# Sheet4.net
KiCad netlist of a schematic drawn in Altium Designer
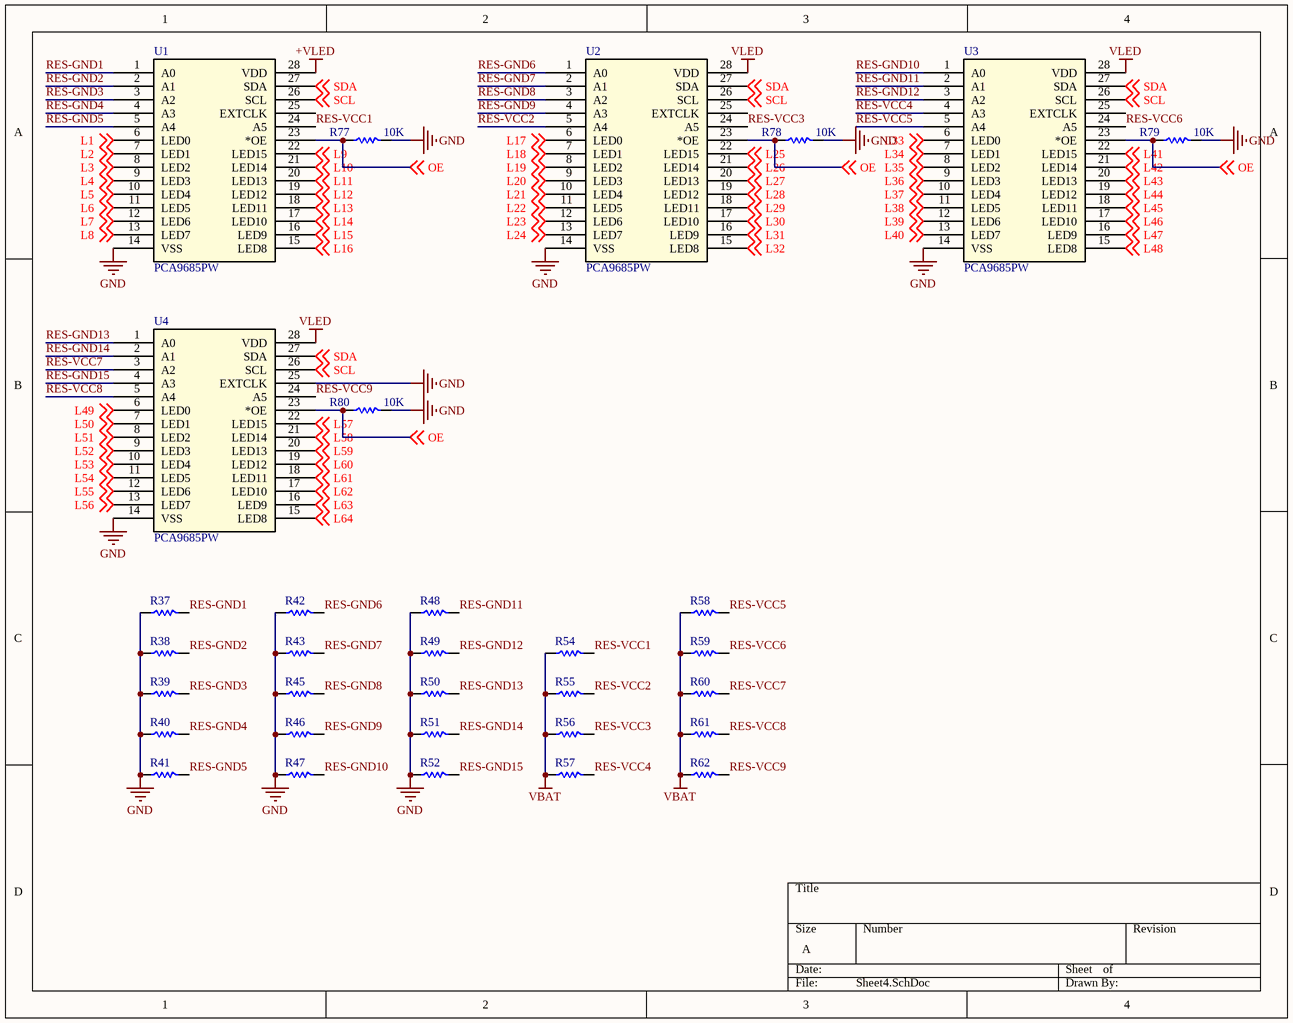
[diagram p0: Sheet4.SchDoc]

(export (version "E")
  (design (tool "Eeschema 10.0.6"))
  (components
    (comp (ref "R37")
      (value "10K")
      (footprint "R 0805")
      (description "Chip resistor")
      (fields (field (name "版权归属") "源创客"))
      (libsource (lib "Passive (Resistor-Capacitor-Inductor-Veristor-Ferrite)") (part "R"))
    )
    (comp (ref "R38")
      (value "10K")
      (footprint "R 0805")
      (description "Chip resistor")
      (fields (field (name "版权归属") "源创客"))
      (libsource (lib "Passive (Resistor-Capacitor-Inductor-Veristor-Ferrite)") (part "R"))
    )
    (comp (ref "R39")
      (value "10K")
      (footprint "R 0805")
      (description "Chip resistor")
      (fields (field (name "版权归属") "源创客"))
      (libsource (lib "Passive (Resistor-Capacitor-Inductor-Veristor-Ferrite)") (part "R"))
    )
    (comp (ref "R40")
      (value "10K")
      (footprint "R 0805")
      (description "Chip resistor")
      (fields (field (name "版权归属") "源创客"))
      (libsource (lib "Passive (Resistor-Capacitor-Inductor-Veristor-Ferrite)") (part "R"))
    )
    (comp (ref "R41")
      (value "10K")
      (footprint "R 0805")
      (description "Chip resistor")
      (fields (field (name "版权归属") "源创客"))
      (libsource (lib "Passive (Resistor-Capacitor-Inductor-Veristor-Ferrite)") (part "R"))
    )
    (comp (ref "R42")
      (value "10K")
      (footprint "R 0805")
      (description "Chip resistor")
      (fields (field (name "版权归属") "源创客"))
      (libsource (lib "Passive (Resistor-Capacitor-Inductor-Veristor-Ferrite)") (part "R"))
    )
    (comp (ref "R43")
      (value "10K")
      (footprint "R 0805")
      (description "Chip resistor")
      (fields (field (name "版权归属") "源创客"))
      (libsource (lib "Passive (Resistor-Capacitor-Inductor-Veristor-Ferrite)") (part "R"))
    )
    (comp (ref "R45")
      (value "10K")
      (footprint "R 0805")
      (description "Chip resistor")
      (fields (field (name "版权归属") "源创客"))
      (libsource (lib "Passive (Resistor-Capacitor-Inductor-Veristor-Ferrite)") (part "R"))
    )
    (comp (ref "R46")
      (value "10K")
      (footprint "R 0805")
      (description "Chip resistor")
      (fields (field (name "版权归属") "源创客"))
      (libsource (lib "Passive (Resistor-Capacitor-Inductor-Veristor-Ferrite)") (part "R"))
    )
    (comp (ref "R47")
      (value "10K")
      (footprint "R 0805")
      (description "Chip resistor")
      (fields (field (name "版权归属") "源创客"))
      (libsource (lib "Passive (Resistor-Capacitor-Inductor-Veristor-Ferrite)") (part "R"))
    )
    (comp (ref "R48")
      (value "10K")
      (footprint "R 0805")
      (description "Chip resistor")
      (fields (field (name "版权归属") "源创客"))
      (libsource (lib "Passive (Resistor-Capacitor-Inductor-Veristor-Ferrite)") (part "R"))
    )
    (comp (ref "R49")
      (value "10K")
      (footprint "R 0805")
      (description "Chip resistor")
      (fields (field (name "版权归属") "源创客"))
      (libsource (lib "Passive (Resistor-Capacitor-Inductor-Veristor-Ferrite)") (part "R"))
    )
    (comp (ref "R50")
      (value "10K")
      (footprint "R 0805")
      (description "Chip resistor")
      (fields (field (name "版权归属") "源创客"))
      (libsource (lib "Passive (Resistor-Capacitor-Inductor-Veristor-Ferrite)") (part "R"))
    )
    (comp (ref "R51")
      (value "10K")
      (footprint "R 0805")
      (description "Chip resistor")
      (fields (field (name "版权归属") "源创客"))
      (libsource (lib "Passive (Resistor-Capacitor-Inductor-Veristor-Ferrite)") (part "R"))
    )
    (comp (ref "R52")
      (value "10K")
      (footprint "R 0805")
      (description "Chip resistor")
      (fields (field (name "版权归属") "源创客"))
      (libsource (lib "Passive (Resistor-Capacitor-Inductor-Veristor-Ferrite)") (part "R"))
    )
    (comp (ref "R54")
      (value "10K")
      (footprint "R 0805")
      (description "Chip resistor")
      (fields (field (name "版权归属") "源创客"))
      (libsource (lib "Passive (Resistor-Capacitor-Inductor-Veristor-Ferrite)") (part "R"))
    )
    (comp (ref "R55")
      (value "10K")
      (footprint "R 0805")
      (description "Chip resistor")
      (fields (field (name "版权归属") "源创客"))
      (libsource (lib "Passive (Resistor-Capacitor-Inductor-Veristor-Ferrite)") (part "R"))
    )
    (comp (ref "R56")
      (value "10K")
      (footprint "R 0805")
      (description "Chip resistor")
      (fields (field (name "版权归属") "源创客"))
      (libsource (lib "Passive (Resistor-Capacitor-Inductor-Veristor-Ferrite)") (part "R"))
    )
    (comp (ref "R57")
      (value "10K")
      (footprint "R 0805")
      (description "Chip resistor")
      (fields (field (name "版权归属") "源创客"))
      (libsource (lib "Passive (Resistor-Capacitor-Inductor-Veristor-Ferrite)") (part "R"))
    )
    (comp (ref "R58")
      (value "10K")
      (footprint "R 0805")
      (description "Chip resistor")
      (fields (field (name "版权归属") "源创客"))
      (libsource (lib "Passive (Resistor-Capacitor-Inductor-Veristor-Ferrite)") (part "R"))
    )
    (comp (ref "R59")
      (value "10K")
      (footprint "R 0805")
      (description "Chip resistor")
      (fields (field (name "版权归属") "源创客"))
      (libsource (lib "Passive (Resistor-Capacitor-Inductor-Veristor-Ferrite)") (part "R"))
    )
    (comp (ref "R60")
      (value "10K")
      (footprint "R 0805")
      (description "Chip resistor")
      (fields (field (name "版权归属") "源创客"))
      (libsource (lib "Passive (Resistor-Capacitor-Inductor-Veristor-Ferrite)") (part "R"))
    )
    (comp (ref "R61")
      (value "10K")
      (footprint "R 0805")
      (description "Chip resistor")
      (fields (field (name "版权归属") "源创客"))
      (libsource (lib "Passive (Resistor-Capacitor-Inductor-Veristor-Ferrite)") (part "R"))
    )
    (comp (ref "R62")
      (value "10K")
      (footprint "R 0805")
      (description "Chip resistor")
      (fields (field (name "版权归属") "源创客"))
      (libsource (lib "Passive (Resistor-Capacitor-Inductor-Veristor-Ferrite)") (part "R"))
    )
    (comp (ref "R77")
      (value "10K")
      (footprint "R 0805")
      (description "Chip resistor")
      (fields (field (name "版权归属") "源创客"))
      (libsource (lib "Passive (Resistor-Capacitor-Inductor-Veristor-Ferrite)") (part "R"))
    )
    (comp (ref "R78")
      (value "10K")
      (footprint "R 0805")
      (description "Chip resistor")
      (fields (field (name "版权归属") "源创客"))
      (libsource (lib "Passive (Resistor-Capacitor-Inductor-Veristor-Ferrite)") (part "R"))
    )
    (comp (ref "R79")
      (value "10K")
      (footprint "R 0805")
      (description "Chip resistor")
      (fields (field (name "版权归属") "源创客"))
      (libsource (lib "Passive (Resistor-Capacitor-Inductor-Veristor-Ferrite)") (part "R"))
    )
    (comp (ref "R80")
      (value "10K")
      (footprint "R 0805")
      (description "Chip resistor")
      (fields (field (name "版权归属") "源创客"))
      (libsource (lib "Passive (Resistor-Capacitor-Inductor-Veristor-Ferrite)") (part "R"))
    )
    (comp (ref "U1")
      (value "PCA9685PW")
      (footprint "SOT361-1_NXP")
      (description "No Description Available")
      (fields (field (name "COPYRIGHT") "Copyright (C) 2018 Accelerated Designs. All rights reserved"))
      (libsource (lib "PCA9685") (part "PCA9685PW"))
    )
    (comp (ref "U2")
      (value "PCA9685PW")
      (footprint "SOT361-1_NXP")
      (description "No Description Available")
      (fields (field (name "COPYRIGHT") "Copyright (C) 2018 Accelerated Designs. All rights reserved"))
      (libsource (lib "PCA9685") (part "PCA9685PW"))
    )
    (comp (ref "U3")
      (value "PCA9685PW")
      (footprint "SOT361-1_NXP")
      (description "No Description Available")
      (fields (field (name "COPYRIGHT") "Copyright (C) 2018 Accelerated Designs. All rights reserved"))
      (libsource (lib "PCA9685") (part "PCA9685PW"))
    )
    (comp (ref "U4")
      (value "PCA9685PW")
      (footprint "SOT361-1_NXP")
      (description "No Description Available")
      (fields (field (name "COPYRIGHT") "Copyright (C) 2018 Accelerated Designs. All rights reserved"))
      (libsource (lib "PCA9685") (part "PCA9685PW"))
    )
  )
  (nets
    (net (code "1") (name "+VLED") (class "Default")
      (node (ref "U1") (pin "28") (pinfunction "VDD_28") (pintype "passive"))
    )
    (net (code "2") (name "/RES-GND1") (class "Default")
      (node (ref "R37") (pin "2") (pinfunction "2_2") (pintype "passive"))
      (node (ref "U1") (pin "1") (pinfunction "A0_1") (pintype "passive"))
    )
    (net (code "3") (name "/RES-GND2") (class "Default")
      (node (ref "R38") (pin "2") (pinfunction "2_2") (pintype "passive"))
      (node (ref "U1") (pin "2") (pinfunction "A1_2") (pintype "passive"))
    )
    (net (code "4") (name "/RES-GND3") (class "Default")
      (node (ref "R39") (pin "2") (pinfunction "2_2") (pintype "passive"))
      (node (ref "U1") (pin "3") (pinfunction "A2_3") (pintype "passive"))
    )
    (net (code "5") (name "/RES-GND4") (class "Default")
      (node (ref "R40") (pin "2") (pinfunction "2_2") (pintype "passive"))
      (node (ref "U1") (pin "4") (pinfunction "A3_4") (pintype "passive"))
    )
    (net (code "6") (name "/RES-GND5") (class "Default")
      (node (ref "R41") (pin "2") (pinfunction "2_2") (pintype "passive"))
      (node (ref "U1") (pin "5") (pinfunction "A4_5") (pintype "passive"))
    )
    (net (code "7") (name "/RES-GND6") (class "Default")
      (node (ref "R42") (pin "2") (pinfunction "2_2") (pintype "passive"))
      (node (ref "U2") (pin "1") (pinfunction "A0_1") (pintype "passive"))
    )
    (net (code "8") (name "/RES-GND7") (class "Default")
      (node (ref "R43") (pin "2") (pinfunction "2_2") (pintype "passive"))
      (node (ref "U2") (pin "2") (pinfunction "A1_2") (pintype "passive"))
    )
    (net (code "9") (name "/RES-GND8") (class "Default")
      (node (ref "R45") (pin "2") (pinfunction "2_2") (pintype "passive"))
      (node (ref "U2") (pin "3") (pinfunction "A2_3") (pintype "passive"))
    )
    (net (code "10") (name "/RES-GND9") (class "Default")
      (node (ref "R46") (pin "2") (pinfunction "2_2") (pintype "passive"))
      (node (ref "U2") (pin "4") (pinfunction "A3_4") (pintype "passive"))
    )
    (net (code "11") (name "/RES-GND10") (class "Default")
      (node (ref "R47") (pin "2") (pinfunction "2_2") (pintype "passive"))
      (node (ref "U3") (pin "1") (pinfunction "A0_1") (pintype "passive"))
    )
    (net (code "12") (name "/RES-GND11") (class "Default")
      (node (ref "R48") (pin "2") (pinfunction "2_2") (pintype "passive"))
      (node (ref "U3") (pin "2") (pinfunction "A1_2") (pintype "passive"))
    )
    (net (code "13") (name "/RES-GND12") (class "Default")
      (node (ref "R49") (pin "2") (pinfunction "2_2") (pintype "passive"))
      (node (ref "U3") (pin "3") (pinfunction "A2_3") (pintype "passive"))
    )
    (net (code "14") (name "/RES-GND13") (class "Default")
      (node (ref "R50") (pin "2") (pinfunction "2_2") (pintype "passive"))
      (node (ref "U4") (pin "1") (pinfunction "A0_1") (pintype "passive"))
    )
    (net (code "15") (name "/RES-GND14") (class "Default")
      (node (ref "R51") (pin "2") (pinfunction "2_2") (pintype "passive"))
      (node (ref "U4") (pin "2") (pinfunction "A1_2") (pintype "passive"))
    )
    (net (code "16") (name "/RES-GND15") (class "Default")
      (node (ref "R52") (pin "2") (pinfunction "2_2") (pintype "passive"))
      (node (ref "U4") (pin "4") (pinfunction "A3_4") (pintype "passive"))
    )
    (net (code "17") (name "/RES-VCC1") (class "Default")
      (node (ref "R54") (pin "2") (pinfunction "2_2") (pintype "passive"))
      (node (ref "U1") (pin "24") (pinfunction "A5_24") (pintype "passive"))
    )
    (net (code "18") (name "/RES-VCC2") (class "Default")
      (node (ref "R55") (pin "2") (pinfunction "2_2") (pintype "passive"))
      (node (ref "U2") (pin "5") (pinfunction "A4_5") (pintype "passive"))
    )
    (net (code "19") (name "/RES-VCC3") (class "Default")
      (node (ref "R56") (pin "2") (pinfunction "2_2") (pintype "passive"))
      (node (ref "U2") (pin "24") (pinfunction "A5_24") (pintype "passive"))
    )
    (net (code "20") (name "/RES-VCC4") (class "Default")
      (node (ref "R57") (pin "2") (pinfunction "2_2") (pintype "passive"))
      (node (ref "U3") (pin "4") (pinfunction "A3_4") (pintype "passive"))
    )
    (net (code "21") (name "/RES-VCC5") (class "Default")
      (node (ref "R58") (pin "2") (pinfunction "2_2") (pintype "passive"))
      (node (ref "U3") (pin "5") (pinfunction "A4_5") (pintype "passive"))
    )
    (net (code "22") (name "/RES-VCC6") (class "Default")
      (node (ref "R59") (pin "2") (pinfunction "2_2") (pintype "passive"))
      (node (ref "U3") (pin "24") (pinfunction "A5_24") (pintype "passive"))
    )
    (net (code "23") (name "/RES-VCC7") (class "Default")
      (node (ref "R60") (pin "2") (pinfunction "2_2") (pintype "passive"))
      (node (ref "U4") (pin "3") (pinfunction "A2_3") (pintype "passive"))
    )
    (net (code "24") (name "/RES-VCC8") (class "Default")
      (node (ref "R61") (pin "2") (pinfunction "2_2") (pintype "passive"))
      (node (ref "U4") (pin "5") (pinfunction "A4_5") (pintype "passive"))
    )
    (net (code "25") (name "/RES-VCC9") (class "Default")
      (node (ref "R62") (pin "2") (pinfunction "2_2") (pintype "passive"))
      (node (ref "U4") (pin "24") (pinfunction "A5_24") (pintype "passive"))
    )
    (net (code "26") (name "GND") (class "Default")
      (node (ref "R37") (pin "1") (pinfunction "1_1") (pintype "passive"))
      (node (ref "R38") (pin "1") (pinfunction "1_1") (pintype "passive"))
      (node (ref "R39") (pin "1") (pinfunction "1_1") (pintype "passive"))
      (node (ref "R40") (pin "1") (pinfunction "1_1") (pintype "passive"))
      (node (ref "R41") (pin "1") (pinfunction "1_1") (pintype "passive"))
      (node (ref "R42") (pin "1") (pinfunction "1_1") (pintype "passive"))
      (node (ref "R43") (pin "1") (pinfunction "1_1") (pintype "passive"))
      (node (ref "R45") (pin "1") (pinfunction "1_1") (pintype "passive"))
      (node (ref "R46") (pin "1") (pinfunction "1_1") (pintype "passive"))
      (node (ref "R47") (pin "1") (pinfunction "1_1") (pintype "passive"))
      (node (ref "R48") (pin "1") (pinfunction "1_1") (pintype "passive"))
      (node (ref "R49") (pin "1") (pinfunction "1_1") (pintype "passive"))
      (node (ref "R50") (pin "1") (pinfunction "1_1") (pintype "passive"))
      (node (ref "R51") (pin "1") (pinfunction "1_1") (pintype "passive"))
      (node (ref "R52") (pin "1") (pinfunction "1_1") (pintype "passive"))
      (node (ref "R77") (pin "2") (pinfunction "2_2") (pintype "passive"))
      (node (ref "R78") (pin "2") (pinfunction "2_2") (pintype "passive"))
      (node (ref "R79") (pin "2") (pinfunction "2_2") (pintype "passive"))
      (node (ref "R80") (pin "2") (pinfunction "2_2") (pintype "passive"))
      (node (ref "U1") (pin "14") (pinfunction "VSS_14") (pintype "passive"))
      (node (ref "U2") (pin "14") (pinfunction "VSS_14") (pintype "passive"))
      (node (ref "U3") (pin "14") (pinfunction "VSS_14") (pintype "passive"))
      (node (ref "U4") (pin "14") (pinfunction "VSS_14") (pintype "passive"))
      (node (ref "U4") (pin "25") (pinfunction "EXTCLK_25") (pintype "passive"))
    )
    (net (code "27") (name "L1") (class "Default")
      (node (ref "U1") (pin "6") (pinfunction "LED0_6") (pintype "passive"))
    )
    (net (code "28") (name "L2") (class "Default")
      (node (ref "U1") (pin "7") (pinfunction "LED1_7") (pintype "passive"))
    )
    (net (code "29") (name "L3") (class "Default")
      (node (ref "U1") (pin "8") (pinfunction "LED2_8") (pintype "passive"))
    )
    (net (code "30") (name "L4") (class "Default")
      (node (ref "U1") (pin "9") (pinfunction "LED3_9") (pintype "passive"))
    )
    (net (code "31") (name "L5") (class "Default")
      (node (ref "U1") (pin "10") (pinfunction "LED4_10") (pintype "passive"))
    )
    (net (code "32") (name "L6") (class "Default")
      (node (ref "U1") (pin "11") (pinfunction "LED5_11") (pintype "passive"))
    )
    (net (code "33") (name "L7") (class "Default")
      (node (ref "U1") (pin "12") (pinfunction "LED6_12") (pintype "passive"))
    )
    (net (code "34") (name "L8") (class "Default")
      (node (ref "U1") (pin "13") (pinfunction "LED7_13") (pintype "passive"))
    )
    (net (code "35") (name "L9") (class "Default")
      (node (ref "U1") (pin "22") (pinfunction "LED15_22") (pintype "passive"))
    )
    (net (code "36") (name "L10") (class "Default")
      (node (ref "U1") (pin "21") (pinfunction "LED14_21") (pintype "passive"))
    )
    (net (code "37") (name "L11") (class "Default")
      (node (ref "U1") (pin "20") (pinfunction "LED13_20") (pintype "passive"))
    )
    (net (code "38") (name "L12") (class "Default")
      (node (ref "U1") (pin "19") (pinfunction "LED12_19") (pintype "passive"))
    )
    (net (code "39") (name "L13") (class "Default")
      (node (ref "U1") (pin "18") (pinfunction "LED11_18") (pintype "passive"))
    )
    (net (code "40") (name "L14") (class "Default")
      (node (ref "U1") (pin "17") (pinfunction "LED10_17") (pintype "passive"))
    )
    (net (code "41") (name "L15") (class "Default")
      (node (ref "U1") (pin "16") (pinfunction "LED9_16") (pintype "passive"))
    )
    (net (code "42") (name "L16") (class "Default")
      (node (ref "U1") (pin "15") (pinfunction "LED8_15") (pintype "passive"))
    )
    (net (code "43") (name "L17") (class "Default")
      (node (ref "U2") (pin "6") (pinfunction "LED0_6") (pintype "passive"))
    )
    (net (code "44") (name "L18") (class "Default")
      (node (ref "U2") (pin "7") (pinfunction "LED1_7") (pintype "passive"))
    )
    (net (code "45") (name "L19") (class "Default")
      (node (ref "U2") (pin "8") (pinfunction "LED2_8") (pintype "passive"))
    )
    (net (code "46") (name "L20") (class "Default")
      (node (ref "U2") (pin "9") (pinfunction "LED3_9") (pintype "passive"))
    )
    (net (code "47") (name "L21") (class "Default")
      (node (ref "U2") (pin "10") (pinfunction "LED4_10") (pintype "passive"))
    )
    (net (code "48") (name "L22") (class "Default")
      (node (ref "U2") (pin "11") (pinfunction "LED5_11") (pintype "passive"))
    )
    (net (code "49") (name "L23") (class "Default")
      (node (ref "U2") (pin "12") (pinfunction "LED6_12") (pintype "passive"))
    )
    (net (code "50") (name "L24") (class "Default")
      (node (ref "U2") (pin "13") (pinfunction "LED7_13") (pintype "passive"))
    )
    (net (code "51") (name "L25") (class "Default")
      (node (ref "U2") (pin "22") (pinfunction "LED15_22") (pintype "passive"))
    )
    (net (code "52") (name "L26") (class "Default")
      (node (ref "U2") (pin "21") (pinfunction "LED14_21") (pintype "passive"))
    )
    (net (code "53") (name "L27") (class "Default")
      (node (ref "U2") (pin "20") (pinfunction "LED13_20") (pintype "passive"))
    )
    (net (code "54") (name "L28") (class "Default")
      (node (ref "U2") (pin "19") (pinfunction "LED12_19") (pintype "passive"))
    )
    (net (code "55") (name "L29") (class "Default")
      (node (ref "U2") (pin "18") (pinfunction "LED11_18") (pintype "passive"))
    )
    (net (code "56") (name "L30") (class "Default")
      (node (ref "U2") (pin "17") (pinfunction "LED10_17") (pintype "passive"))
    )
    (net (code "57") (name "L31") (class "Default")
      (node (ref "U2") (pin "16") (pinfunction "LED9_16") (pintype "passive"))
    )
    (net (code "58") (name "L32") (class "Default")
      (node (ref "U2") (pin "15") (pinfunction "LED8_15") (pintype "passive"))
    )
    (net (code "59") (name "L33") (class "Default")
      (node (ref "U3") (pin "6") (pinfunction "LED0_6") (pintype "passive"))
    )
    (net (code "60") (name "L34") (class "Default")
      (node (ref "U3") (pin "7") (pinfunction "LED1_7") (pintype "passive"))
    )
    (net (code "61") (name "L35") (class "Default")
      (node (ref "U3") (pin "8") (pinfunction "LED2_8") (pintype "passive"))
    )
    (net (code "62") (name "L36") (class "Default")
      (node (ref "U3") (pin "9") (pinfunction "LED3_9") (pintype "passive"))
    )
    (net (code "63") (name "L37") (class "Default")
      (node (ref "U3") (pin "10") (pinfunction "LED4_10") (pintype "passive"))
    )
    (net (code "64") (name "L38") (class "Default")
      (node (ref "U3") (pin "11") (pinfunction "LED5_11") (pintype "passive"))
    )
    (net (code "65") (name "L39") (class "Default")
      (node (ref "U3") (pin "12") (pinfunction "LED6_12") (pintype "passive"))
    )
    (net (code "66") (name "L40") (class "Default")
      (node (ref "U3") (pin "13") (pinfunction "LED7_13") (pintype "passive"))
    )
    (net (code "67") (name "L41") (class "Default")
      (node (ref "U3") (pin "22") (pinfunction "LED15_22") (pintype "passive"))
    )
    (net (code "68") (name "L42") (class "Default")
      (node (ref "U3") (pin "21") (pinfunction "LED14_21") (pintype "passive"))
    )
    (net (code "69") (name "L43") (class "Default")
      (node (ref "U3") (pin "20") (pinfunction "LED13_20") (pintype "passive"))
    )
    (net (code "70") (name "L44") (class "Default")
      (node (ref "U3") (pin "19") (pinfunction "LED12_19") (pintype "passive"))
    )
    (net (code "71") (name "L45") (class "Default")
      (node (ref "U3") (pin "18") (pinfunction "LED11_18") (pintype "passive"))
    )
    (net (code "72") (name "L46") (class "Default")
      (node (ref "U3") (pin "17") (pinfunction "LED10_17") (pintype "passive"))
    )
    (net (code "73") (name "L47") (class "Default")
      (node (ref "U3") (pin "16") (pinfunction "LED9_16") (pintype "passive"))
    )
    (net (code "74") (name "L48") (class "Default")
      (node (ref "U3") (pin "15") (pinfunction "LED8_15") (pintype "passive"))
    )
    (net (code "75") (name "L49") (class "Default")
      (node (ref "U4") (pin "6") (pinfunction "LED0_6") (pintype "passive"))
    )
    (net (code "76") (name "L50") (class "Default")
      (node (ref "U4") (pin "7") (pinfunction "LED1_7") (pintype "passive"))
    )
    (net (code "77") (name "L51") (class "Default")
      (node (ref "U4") (pin "8") (pinfunction "LED2_8") (pintype "passive"))
    )
    (net (code "78") (name "L52") (class "Default")
      (node (ref "U4") (pin "9") (pinfunction "LED3_9") (pintype "passive"))
    )
    (net (code "79") (name "L53") (class "Default")
      (node (ref "U4") (pin "10") (pinfunction "LED4_10") (pintype "passive"))
    )
    (net (code "80") (name "L54") (class "Default")
      (node (ref "U4") (pin "11") (pinfunction "LED5_11") (pintype "passive"))
    )
    (net (code "81") (name "L55") (class "Default")
      (node (ref "U4") (pin "12") (pinfunction "LED6_12") (pintype "passive"))
    )
    (net (code "82") (name "L56") (class "Default")
      (node (ref "U4") (pin "13") (pinfunction "LED7_13") (pintype "passive"))
    )
    (net (code "83") (name "L57") (class "Default")
      (node (ref "U4") (pin "22") (pinfunction "LED15_22") (pintype "passive"))
    )
    (net (code "84") (name "L58") (class "Default")
      (node (ref "U4") (pin "21") (pinfunction "LED14_21") (pintype "passive"))
    )
    (net (code "85") (name "L59") (class "Default")
      (node (ref "U4") (pin "20") (pinfunction "LED13_20") (pintype "passive"))
    )
    (net (code "86") (name "L60") (class "Default")
      (node (ref "U4") (pin "19") (pinfunction "LED12_19") (pintype "passive"))
    )
    (net (code "87") (name "L61") (class "Default")
      (node (ref "U4") (pin "18") (pinfunction "LED11_18") (pintype "passive"))
    )
    (net (code "88") (name "L62") (class "Default")
      (node (ref "U4") (pin "17") (pinfunction "LED10_17") (pintype "passive"))
    )
    (net (code "89") (name "L63") (class "Default")
      (node (ref "U4") (pin "16") (pinfunction "LED9_16") (pintype "passive"))
    )
    (net (code "90") (name "L64") (class "Default")
      (node (ref "U4") (pin "15") (pinfunction "LED8_15") (pintype "passive"))
    )
    (net (code "91") (name "OE") (class "Default")
      (node (ref "R77") (pin "1") (pinfunction "1_1") (pintype "passive"))
      (node (ref "R78") (pin "1") (pinfunction "1_1") (pintype "passive"))
      (node (ref "R79") (pin "1") (pinfunction "1_1") (pintype "passive"))
      (node (ref "R80") (pin "1") (pinfunction "1_1") (pintype "passive"))
      (node (ref "U1") (pin "23") (pinfunction "*OE_23") (pintype "passive"))
      (node (ref "U2") (pin "23") (pinfunction "*OE_23") (pintype "passive"))
      (node (ref "U3") (pin "23") (pinfunction "*OE_23") (pintype "passive"))
      (node (ref "U4") (pin "23") (pinfunction "*OE_23") (pintype "passive"))
    )
    (net (code "92") (name "SCL") (class "Default")
      (node (ref "U1") (pin "26") (pinfunction "SCL_26") (pintype "passive"))
      (node (ref "U2") (pin "26") (pinfunction "SCL_26") (pintype "passive"))
      (node (ref "U3") (pin "26") (pinfunction "SCL_26") (pintype "passive"))
      (node (ref "U4") (pin "26") (pinfunction "SCL_26") (pintype "passive"))
    )
    (net (code "93") (name "SDA") (class "Default")
      (node (ref "U1") (pin "27") (pinfunction "SDA_27") (pintype "passive"))
      (node (ref "U2") (pin "27") (pinfunction "SDA_27") (pintype "passive"))
      (node (ref "U3") (pin "27") (pinfunction "SDA_27") (pintype "passive"))
      (node (ref "U4") (pin "27") (pinfunction "SDA_27") (pintype "passive"))
    )
    (net (code "94") (name "VBAT") (class "Default")
      (node (ref "R54") (pin "1") (pinfunction "1_1") (pintype "passive"))
      (node (ref "R55") (pin "1") (pinfunction "1_1") (pintype "passive"))
      (node (ref "R56") (pin "1") (pinfunction "1_1") (pintype "passive"))
      (node (ref "R57") (pin "1") (pinfunction "1_1") (pintype "passive"))
      (node (ref "R58") (pin "1") (pinfunction "1_1") (pintype "passive"))
      (node (ref "R59") (pin "1") (pinfunction "1_1") (pintype "passive"))
      (node (ref "R60") (pin "1") (pinfunction "1_1") (pintype "passive"))
      (node (ref "R61") (pin "1") (pinfunction "1_1") (pintype "passive"))
      (node (ref "R62") (pin "1") (pinfunction "1_1") (pintype "passive"))
    )
    (net (code "95") (name "VLED") (class "Default")
      (node (ref "U2") (pin "28") (pinfunction "VDD_28") (pintype "passive"))
      (node (ref "U3") (pin "28") (pinfunction "VDD_28") (pintype "passive"))
      (node (ref "U4") (pin "28") (pinfunction "VDD_28") (pintype "passive"))
    )
    (net (code "96") (name "unconnected-(U1-EXTCLK-Pad25)") (class "Default")
      (node (ref "U1") (pin "25") (pinfunction "EXTCLK_25") (pintype "passive"))
    )
    (net (code "97") (name "unconnected-(U2-EXTCLK-Pad25)") (class "Default")
      (node (ref "U2") (pin "25") (pinfunction "EXTCLK_25") (pintype "passive"))
    )
    (net (code "98") (name "unconnected-(U3-EXTCLK-Pad25)") (class "Default")
      (node (ref "U3") (pin "25") (pinfunction "EXTCLK_25") (pintype "passive"))
    )
  )
)
